# FV1_Touch.net
KiCad netlist of a schematic drawn in EAGLE
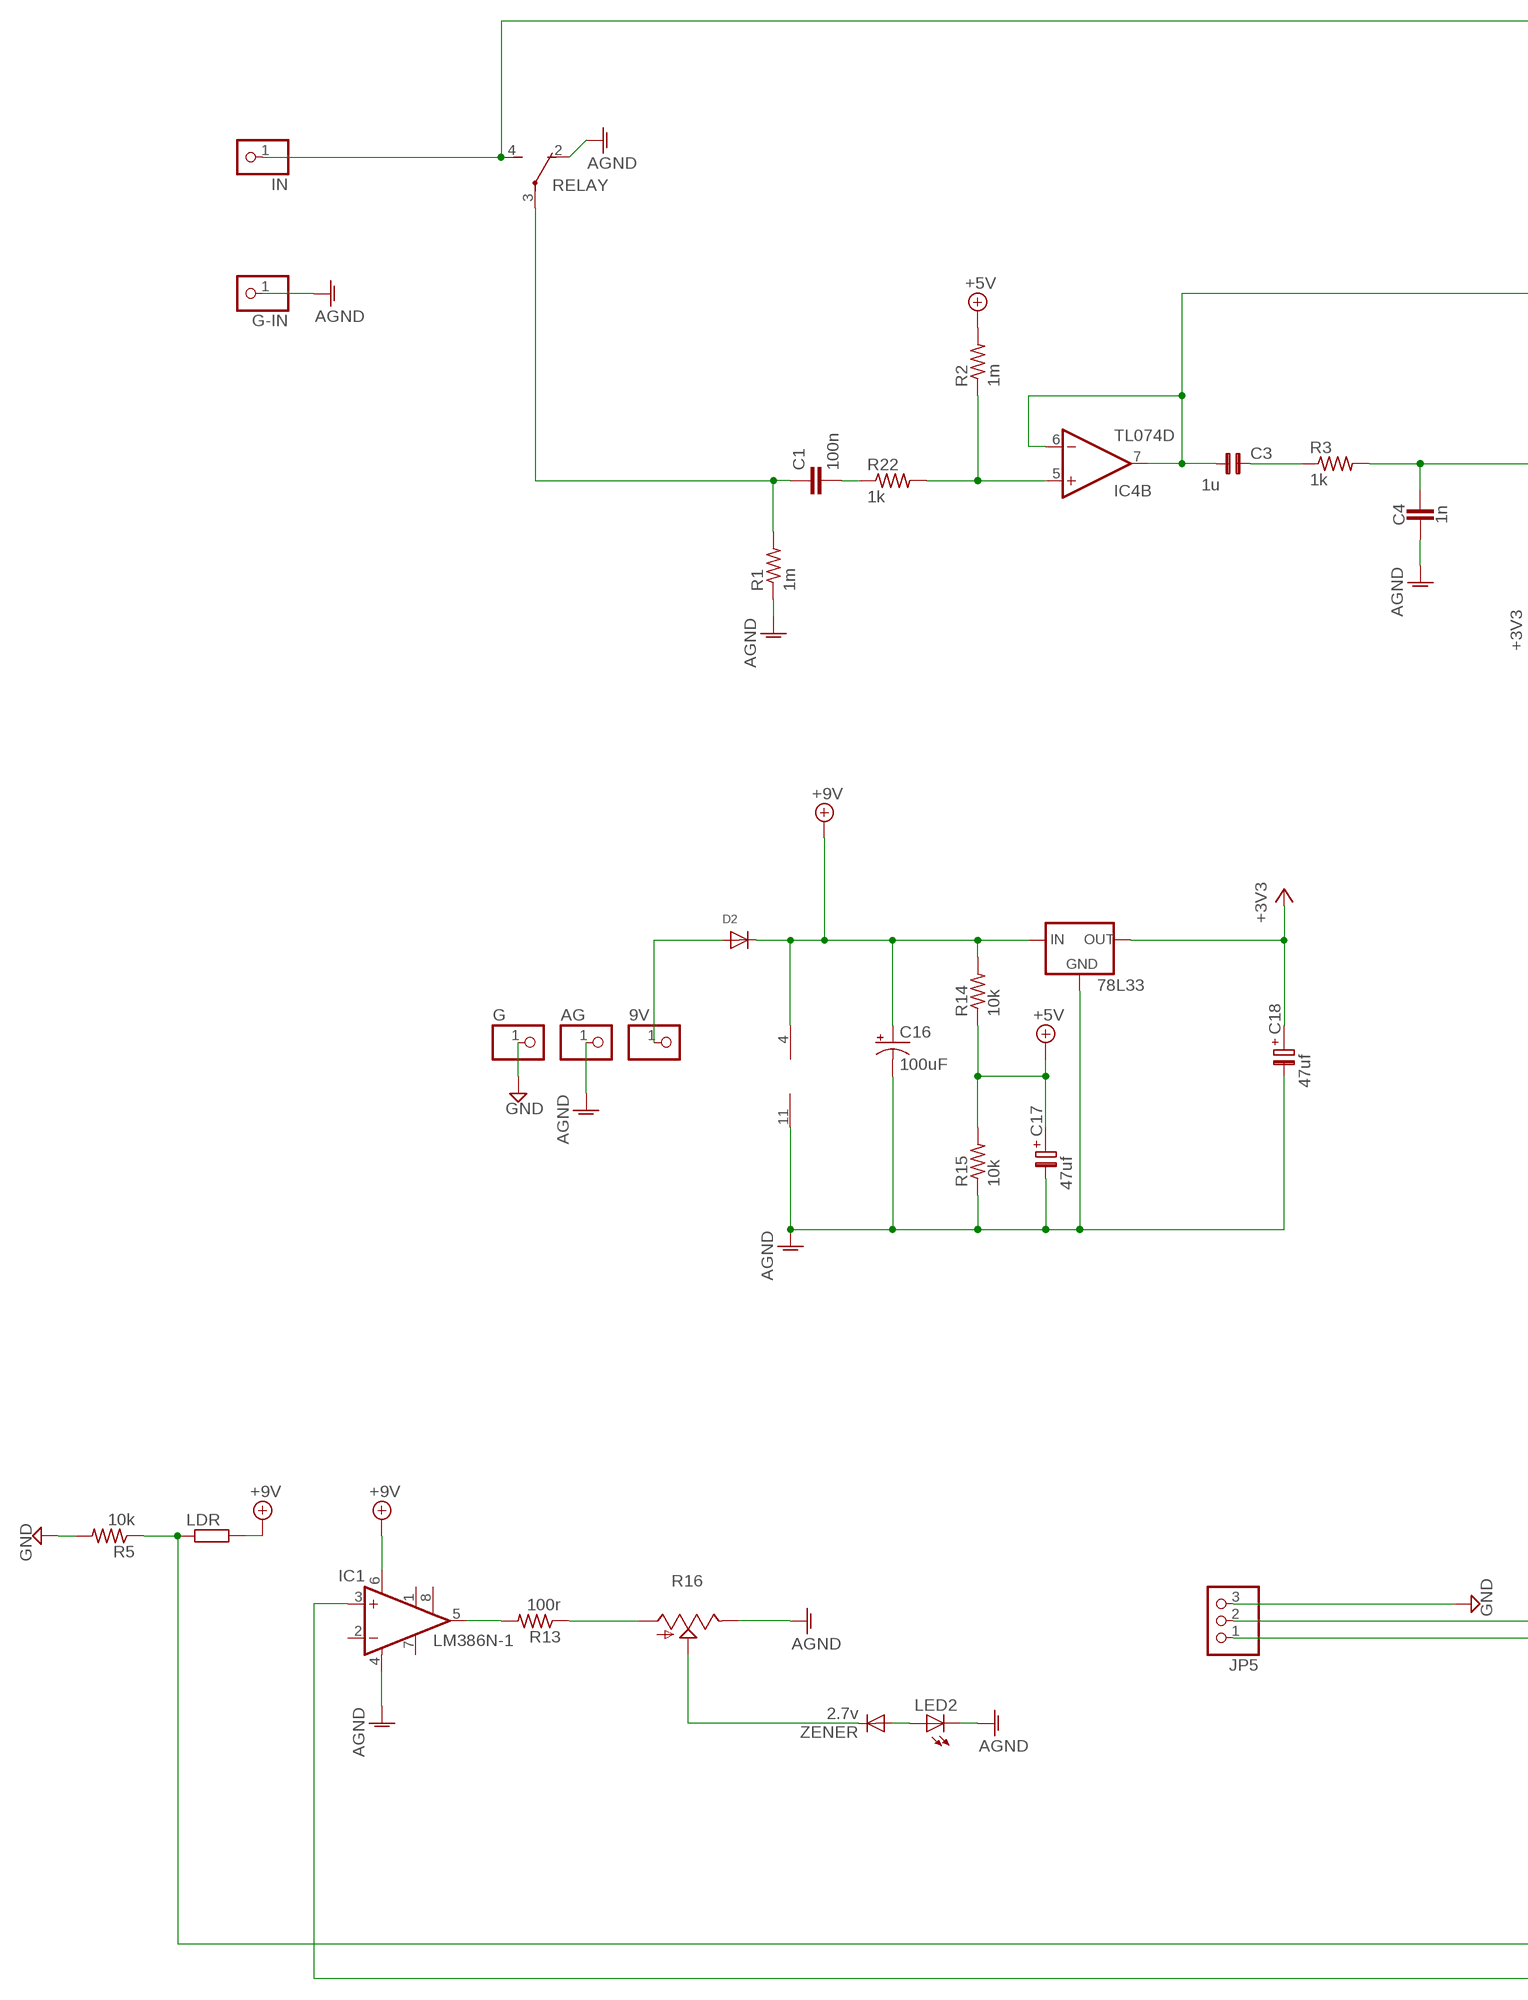
[diagram p0: schematic, sheet 1, part 1 of 2]
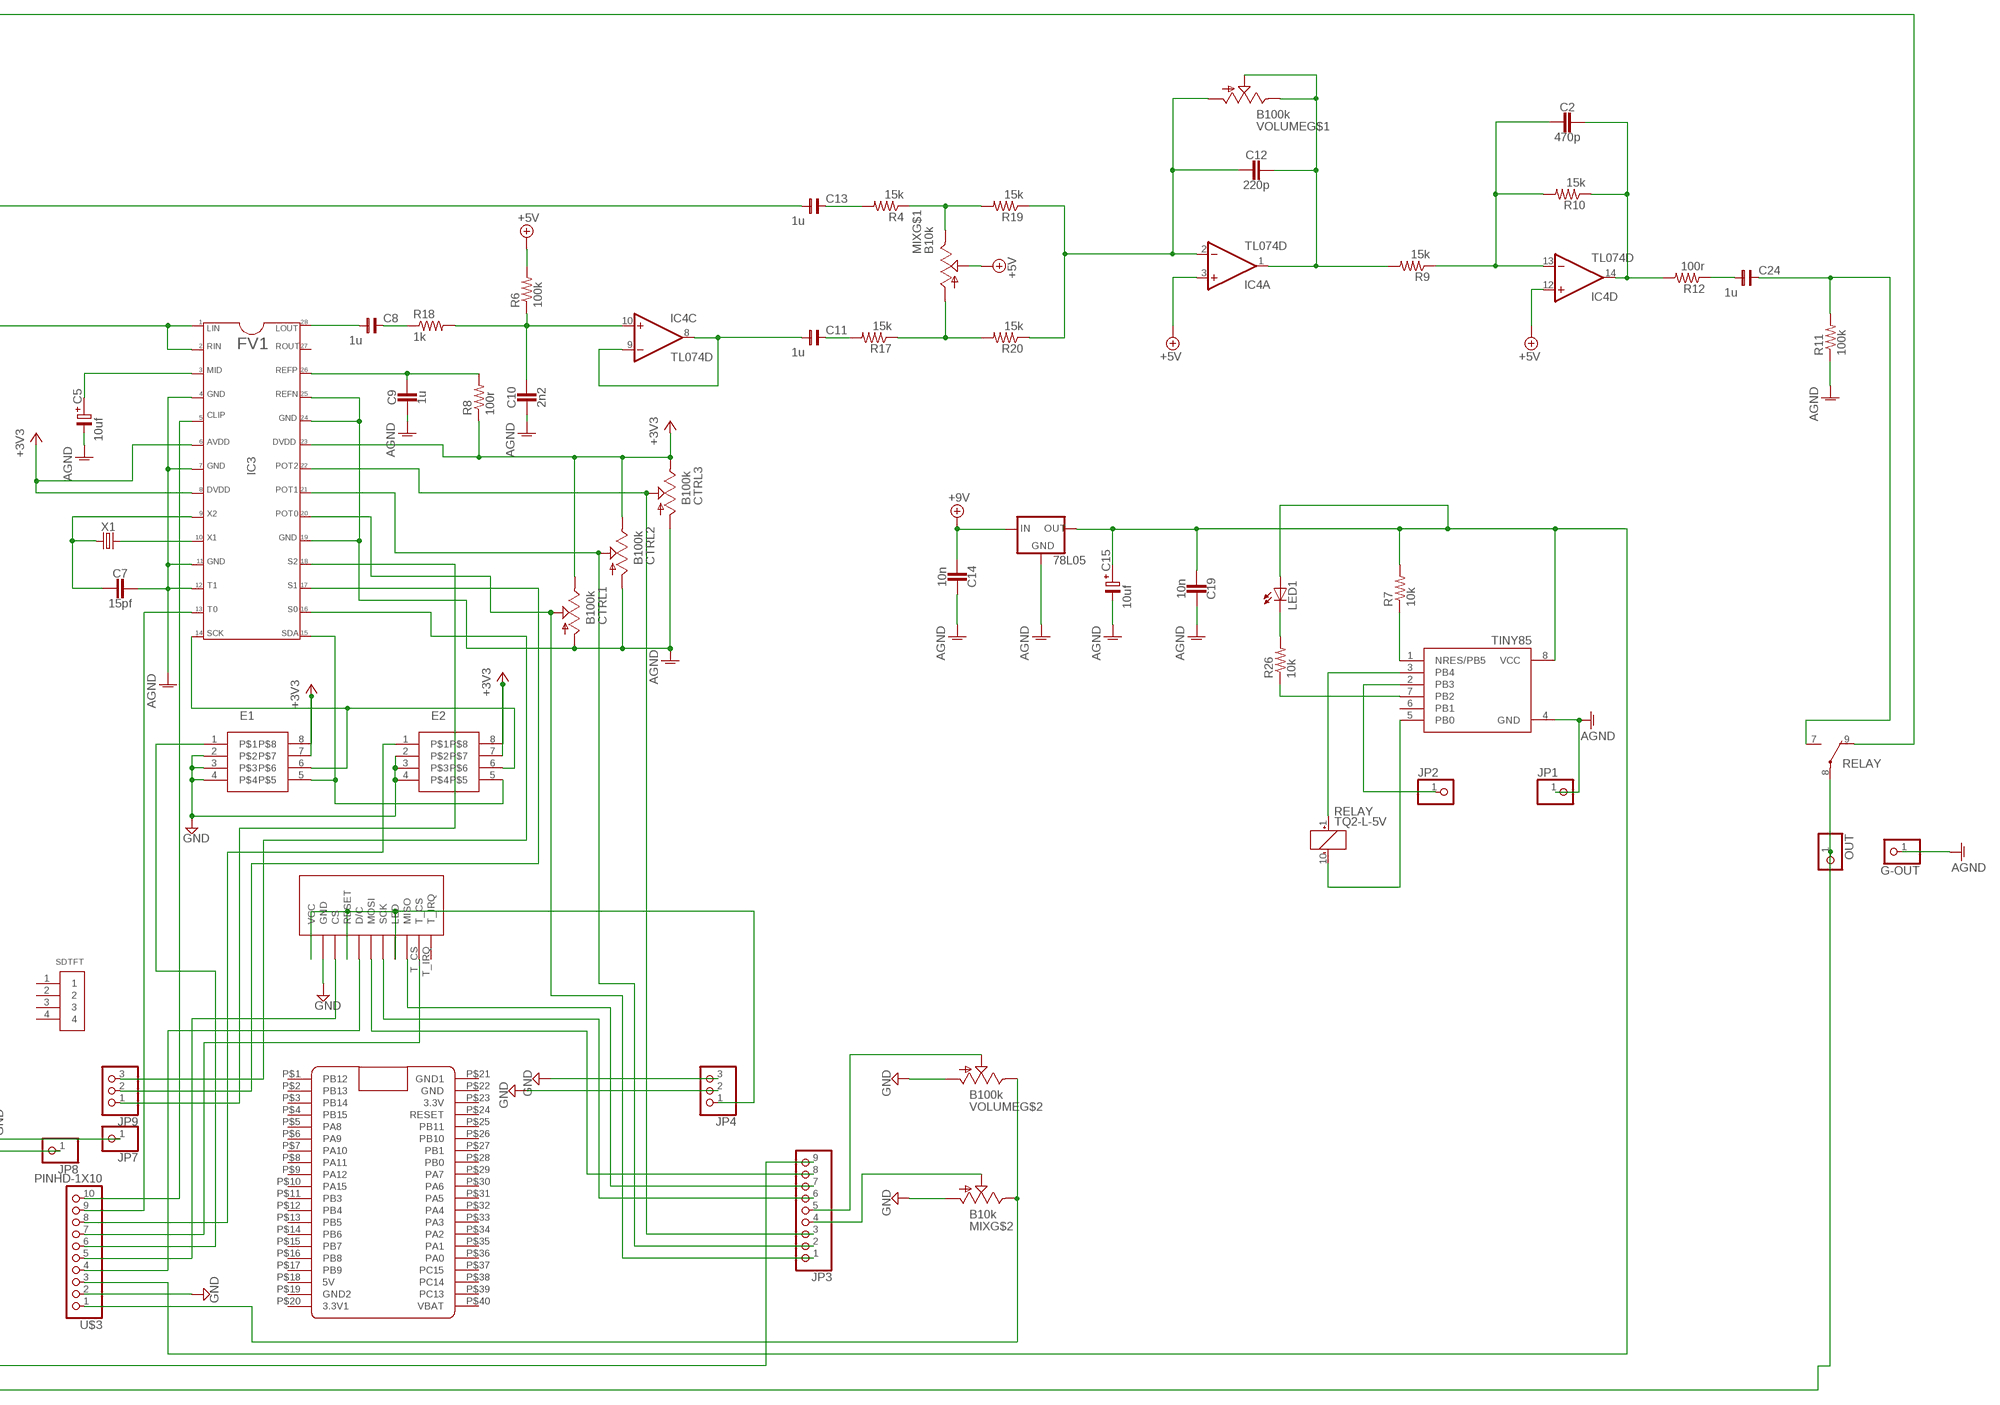
[diagram p1: schematic, sheet 1, part 2 of 2]

(export (version "E")
  (design (tool "Eeschema 10.0.6"))
  (components
    (comp (ref "9V")
      (value "PINHD-1X1")
      (footprint "eagle-import:1X01")
      (libsource (lib "eagle-import") (part "PINHD-1X1"))
    )
    (comp (ref "78L05")
      (value "78LXX-SOT89")
      (footprint "eagle-import:SOT89")
      (libsource (lib "eagle-import") (part "78LXX-SOT89"))
    )
    (comp (ref "78L33")
      (value "78LXX-SOT89")
      (footprint "eagle-import:SOT89")
      (libsource (lib "eagle-import") (part "78LXX-SOT89"))
    )
    (comp (ref "AG")
      (value "PINHD-1X1")
      (footprint "eagle-import:1X01")
      (libsource (lib "eagle-import") (part "PINHD-1X1"))
    )
    (comp (ref "C1")
      (value "100n")
      (footprint "eagle-import:C5B3")
      (libsource (lib "eagle-import") (part "C5/3"))
    )
    (comp (ref "C2")
      (value "470p")
      (footprint "eagle-import:RESISTOR_C1206")
      (libsource (lib "eagle-import") (part "CAP1206"))
    )
    (comp (ref "C3")
      (value "1u")
      (footprint "eagle-import:C5,0-7,5X3,0")
      (libsource (lib "eagle-import") (part "C-NP-5,0-7,5X3,0"))
    )
    (comp (ref "C4")
      (value "1n")
      (footprint "eagle-import:RESISTOR_C1206")
      (libsource (lib "eagle-import") (part "CAP1206"))
    )
    (comp (ref "C5")
      (value "10uf")
      (footprint "eagle-import:SV-C")
      (libsource (lib "eagle-import") (part "C-PR-SMD-SV-C"))
    )
    (comp (ref "C7")
      (value "15pf")
      (footprint "eagle-import:RESISTOR_C1206")
      (libsource (lib "eagle-import") (part "CAP1206"))
    )
    (comp (ref "C8")
      (value "1u")
      (footprint "eagle-import:C5,0-7,5X3,0")
      (libsource (lib "eagle-import") (part "C-NP-5,0-7,5X3,0"))
    )
    (comp (ref "C9")
      (value "1u")
      (footprint "eagle-import:RESISTOR_C1206")
      (libsource (lib "eagle-import") (part "CAP1206"))
    )
    (comp (ref "C10")
      (value "2n2")
      (footprint "eagle-import:RESISTOR_C1206")
      (libsource (lib "eagle-import") (part "CAP1206"))
    )
    (comp (ref "C11")
      (value "1u")
      (footprint "eagle-import:C5,0-7,5X3,0")
      (libsource (lib "eagle-import") (part "C-NP-5,0-7,5X3,0"))
    )
    (comp (ref "C12")
      (value "220p")
      (footprint "eagle-import:RESISTOR_C1206")
      (libsource (lib "eagle-import") (part "CAP1206"))
    )
    (comp (ref "C13")
      (value "1u")
      (footprint "eagle-import:C5,0-7,5X3,0")
      (libsource (lib "eagle-import") (part "C-NP-5,0-7,5X3,0"))
    )
    (comp (ref "C14")
      (value "10n")
      (footprint "eagle-import:RESISTOR_C1206")
      (libsource (lib "eagle-import") (part "CAP1206"))
    )
    (comp (ref "C15")
      (value "10uf")
      (footprint "eagle-import:SV-C")
      (libsource (lib "eagle-import") (part "C-PR-SMD-SV-C"))
    )
    (comp (ref "C16")
      (value "100uF")
      (footprint "eagle-import:PANASONIC_D")
      (libsource (lib "eagle-import") (part "100UF-POLAR-25V-20%(ELEC)"))
    )
    (comp (ref "C17")
      (value "47uf")
      (footprint "eagle-import:SV-C")
      (libsource (lib "eagle-import") (part "C-PR-SMD-SV-C"))
    )
    (comp (ref "C18")
      (value "47uf")
      (footprint "eagle-import:SV-C")
      (libsource (lib "eagle-import") (part "C-PR-SMD-SV-C"))
    )
    (comp (ref "C19")
      (value "10n")
      (footprint "eagle-import:RESISTOR_C1206")
      (libsource (lib "eagle-import") (part "CAP1206"))
    )
    (comp (ref "C24")
      (value "1u")
      (footprint "eagle-import:C5,0-7,5X3,0")
      (libsource (lib "eagle-import") (part "C-NP-5,0-7,5X3,0"))
    )
    (comp (ref "CTRL1")
      (value "B100k")
      (footprint "eagle-import:9MM_SNAP-IN_POT")
      (libsource (lib "eagle-import") (part "9MM_SNAP-IN_POT_"))
    )
    (comp (ref "CTRL2")
      (value "B100k")
      (footprint "eagle-import:9MM_SNAP-IN_POT")
      (libsource (lib "eagle-import") (part "9MM_SNAP-IN_POT_"))
    )
    (comp (ref "CTRL3")
      (value "B100k")
      (footprint "eagle-import:9MM_SNAP-IN_POT")
      (libsource (lib "eagle-import") (part "9MM_SNAP-IN_POT_"))
    )
    (comp (ref "D2")
      (value "DIODESOD-123")
      (footprint "eagle-import:SOD-123")
      (libsource (lib "eagle-import") (part "DIODESOD-123"))
    )
    (comp (ref "E1")
      (value "-EEPROM")
      (footprint "eagle-import:SOCKED-08")
      (libsource (lib "eagle-import") (part "-EEPROM"))
    )
    (comp (ref "E2")
      (value "-EEPROM")
      (footprint "eagle-import:SOCKED-08")
      (libsource (lib "eagle-import") (part "-EEPROM"))
    )
    (comp (ref "G")
      (value "PINHD-1X1")
      (footprint "eagle-import:1X01")
      (libsource (lib "eagle-import") (part "PINHD-1X1"))
    )
    (comp (ref "G-IN")
      (value "PINHD-1X1")
      (footprint "eagle-import:1X01")
      (libsource (lib "eagle-import") (part "PINHD-1X1"))
    )
    (comp (ref "G-OUT")
      (value "PINHD-1X1")
      (footprint "eagle-import:1X01")
      (libsource (lib "eagle-import") (part "PINHD-1X1"))
    )
    (comp (ref "IC1")
      (value "LM386N-1")
      (footprint "eagle-import:DIL08")
      (libsource (lib "eagle-import") (part "LM386?-N1"))
    )
    (comp (ref "IC3")
      (value "FV1")
      (footprint "eagle-import:SO1C28")
      (libsource (lib "eagle-import") (part "FV1"))
    )
    (comp (ref "IC4")
      (value "TL074D")
      (footprint "eagle-import:SO14")
      (libsource (lib "eagle-import") (part "TL074D"))
    )
    (comp (ref "IN")
      (value "PINHD-1X1")
      (footprint "eagle-import:1X01")
      (libsource (lib "eagle-import") (part "PINHD-1X1"))
    )
    (comp (ref "J1")
      (value "SPI_TFT_DISPLAY_TOUCH")
      (footprint "eagle-import:SPI_DISPLAY_TOUCH")
      (libsource (lib "eagle-import") (part "SPI_TFT_DISPLAY_TOUCH"))
    )
    (comp (ref "JP1")
      (value "PINHD-1X1CB")
      (footprint "eagle-import:1X01-CLEANBIG")
      (libsource (lib "eagle-import") (part "PINHD-1X1CB"))
    )
    (comp (ref "JP2")
      (value "PINHD-1X1CB")
      (footprint "eagle-import:1X01-CLEANBIG")
      (libsource (lib "eagle-import") (part "PINHD-1X1CB"))
    )
    (comp (ref "JP3")
      (value "PINHD-1X9")
      (footprint "eagle-import:1X09-BIG")
      (libsource (lib "eagle-import") (part "PINHD-1X9"))
    )
    (comp (ref "JP4")
      (value "PINHD-1X3")
      (footprint "eagle-import:1X03")
      (libsource (lib "eagle-import") (part "PINHD-1X3"))
    )
    (comp (ref "JP5")
      (value "PINHD-1X3")
      (footprint "eagle-import:1X03")
      (libsource (lib "eagle-import") (part "PINHD-1X3"))
    )
    (comp (ref "JP7")
      (value "PINHD-1X1")
      (footprint "eagle-import:1X01")
      (libsource (lib "eagle-import") (part "PINHD-1X1"))
    )
    (comp (ref "JP8")
      (value "PINHD-1X1")
      (footprint "eagle-import:1X01")
      (libsource (lib "eagle-import") (part "PINHD-1X1"))
    )
    (comp (ref "JP9")
      (value "PINHD-1X3")
      (footprint "eagle-import:1X03")
      (libsource (lib "eagle-import") (part "PINHD-1X3"))
    )
    (comp (ref "LDR")
      (value "R-EU_0204/5")
      (footprint "eagle-import:0204_5")
      (libsource (lib "eagle-import") (part "R-EU_0204/5"))
    )
    (comp (ref "LED1")
      (value "LED5MM")
      (footprint "eagle-import:LED5MM")
      (libsource (lib "eagle-import") (part "LED5MM"))
    )
    (comp (ref "LED2")
      (value "LED5MM")
      (footprint "eagle-import:LED5MM")
      (libsource (lib "eagle-import") (part "LED5MM"))
    )
    (comp (ref "MIX")
      (value "B10k")
      (footprint "eagle-import:DUAL_9MM_SNAP-IN_POT")
      (libsource (lib "eagle-import") (part "ALPHA-9MM-DUALPOT"))
    )
    (comp (ref "OUT")
      (value "PINHD-1X1")
      (footprint "eagle-import:1X01")
      (libsource (lib "eagle-import") (part "PINHD-1X1"))
    )
    (comp (ref "R1")
      (value "1m")
      (footprint "eagle-import:R0805")
      (libsource (lib "eagle-import") (part "R-US_R0805"))
    )
    (comp (ref "R2")
      (value "1m")
      (footprint "eagle-import:R0805")
      (libsource (lib "eagle-import") (part "R-US_R0805"))
    )
    (comp (ref "R3")
      (value "1k")
      (footprint "eagle-import:R0805")
      (libsource (lib "eagle-import") (part "R-US_R0805"))
    )
    (comp (ref "R4")
      (value "15k")
      (footprint "eagle-import:R0805")
      (libsource (lib "eagle-import") (part "R-US_R0805"))
    )
    (comp (ref "R5")
      (value "10k")
      (footprint "eagle-import:R0805")
      (libsource (lib "eagle-import") (part "R-US_R0805"))
    )
    (comp (ref "R6")
      (value "100k")
      (footprint "eagle-import:R0805")
      (libsource (lib "eagle-import") (part "R-US_R0805"))
    )
    (comp (ref "R7")
      (value "10k")
      (footprint "eagle-import:R0805")
      (libsource (lib "eagle-import") (part "R-US_R0805"))
    )
    (comp (ref "R8")
      (value "100r")
      (footprint "eagle-import:R0805")
      (libsource (lib "eagle-import") (part "R-US_R0805"))
    )
    (comp (ref "R9")
      (value "15k")
      (footprint "eagle-import:R0805")
      (libsource (lib "eagle-import") (part "R-US_R0805"))
    )
    (comp (ref "R10")
      (value "15k")
      (footprint "eagle-import:R0805")
      (libsource (lib "eagle-import") (part "R-US_R0805"))
    )
    (comp (ref "R11")
      (value "100k")
      (footprint "eagle-import:R0805")
      (libsource (lib "eagle-import") (part "R-US_R0805"))
    )
    (comp (ref "R12")
      (value "100r")
      (footprint "eagle-import:R0805")
      (libsource (lib "eagle-import") (part "R-US_R0805"))
    )
    (comp (ref "R13")
      (value "100r")
      (footprint "eagle-import:R0805")
      (libsource (lib "eagle-import") (part "R-US_R0805"))
    )
    (comp (ref "R14")
      (value "10k")
      (footprint "eagle-import:R0805")
      (libsource (lib "eagle-import") (part "R-US_R0805"))
    )
    (comp (ref "R15")
      (value "10k")
      (footprint "eagle-import:R0805")
      (libsource (lib "eagle-import") (part "R-US_R0805"))
    )
    (comp (ref "R16")
      (value "TRIM_US-B25P")
      (footprint "eagle-import:B25P")
      (libsource (lib "eagle-import") (part "TRIM_US-B25P"))
    )
    (comp (ref "R17")
      (value "15k")
      (footprint "eagle-import:R0805")
      (libsource (lib "eagle-import") (part "R-US_R0805"))
    )
    (comp (ref "R18")
      (value "1k")
      (footprint "eagle-import:R0805")
      (libsource (lib "eagle-import") (part "R-US_R0805"))
    )
    (comp (ref "R19")
      (value "15k")
      (footprint "eagle-import:R0805")
      (libsource (lib "eagle-import") (part "R-US_R0805"))
    )
    (comp (ref "R20")
      (value "15k")
      (footprint "eagle-import:R0805")
      (libsource (lib "eagle-import") (part "R-US_R0805"))
    )
    (comp (ref "R22")
      (value "1k")
      (footprint "eagle-import:R0805")
      (libsource (lib "eagle-import") (part "R-US_R0805"))
    )
    (comp (ref "R26")
      (value "10k")
      (footprint "eagle-import:R0805")
      (libsource (lib "eagle-import") (part "R-US_R0805"))
    )
    (comp (ref "RELAY")
      (value "TQ2-L-5V")
      (footprint "eagle-import:TQ2")
      (libsource (lib "eagle-import") (part "TQ2?-5V"))
    )
    (comp (ref "SDTFT")
      (value "1X4-BIG")
      (footprint "eagle-import:1X04-BIG")
      (libsource (lib "eagle-import") (part "1X4-BIG"))
    )
    (comp (ref "TINY85")
      (value "ATTINY85-20P")
      (footprint "eagle-import:PDIP08_300MIL")
      (libsource (lib "eagle-import") (part "ATTINY85P-20"))
    )
    (comp (ref "U$1")
      (value "BLUE_PILL")
      (footprint "eagle-import:BLUE_PILL")
      (libsource (lib "eagle-import") (part "BLUE_PILL"))
    )
    (comp (ref "U$3")
      (value "PINHD-1X10")
      (footprint "eagle-import:1X10-BIG")
      (libsource (lib "eagle-import") (part "PINHD-1X10"))
    )
    (comp (ref "VOLUME")
      (value "B100k")
      (footprint "eagle-import:DUAL_9MM_SNAP-IN_POT")
      (libsource (lib "eagle-import") (part "ALPHA-9MM-DUALPOT"))
    )
    (comp (ref "X1")
      (value "CRYSTALPTH-2X6-KIT")
      (footprint "eagle-import:CRYSTAL-PTH-2X6-CYL-KIT")
      (libsource (lib "eagle-import") (part "CRYSTALPTH-2X6-KIT"))
    )
    (comp (ref "ZENER")
      (value "2.7v")
      (footprint "eagle-import:DO35-7")
      (libsource (lib "eagle-import") (part "SMALL_DIODEDO35-7"))
    )
  )
  (nets
    (net (code "1") (name "+3V3") (class "Default")
      (node (ref "78L33") (pin "1") (pinfunction "OUT_1") (pintype "passive"))
      (node (ref "C18") (pin "+") (pinfunction "+_+") (pintype "passive"))
      (node (ref "CTRL1") (pin "3") (pinfunction "E_3") (pintype "passive"))
      (node (ref "CTRL2") (pin "3") (pinfunction "E_3") (pintype "passive"))
      (node (ref "CTRL3") (pin "3") (pinfunction "E_3") (pintype "passive"))
      (node (ref "E1") (pin "7") (pinfunction "P$7_7") (pintype "bidirectional"))
      (node (ref "E1") (pin "8") (pinfunction "P$8_8") (pintype "bidirectional"))
      (node (ref "E2") (pin "7") (pinfunction "P$7_7") (pintype "bidirectional"))
      (node (ref "E2") (pin "8") (pinfunction "P$8_8") (pintype "bidirectional"))
      (node (ref "IC3") (pin "23") (pinfunction "P$23_23") (pintype "bidirectional"))
      (node (ref "IC3") (pin "6") (pinfunction "P$6_6") (pintype "bidirectional"))
      (node (ref "IC3") (pin "8") (pinfunction "P$8_8") (pintype "bidirectional"))
      (node (ref "R8") (pin "1") (pinfunction "1_1") (pintype "passive"))
    )
    (net (code "2") (name "+5V") (class "Default")
      (node (ref "C17") (pin "+") (pinfunction "+_+") (pintype "passive"))
      (node (ref "IC4") (pin "12") (pinfunction "+IN_12") (pintype "input"))
      (node (ref "IC4") (pin "3") (pinfunction "+IN_3") (pintype "input"))
      (node (ref "MIX") (pin "2") (pinfunction "S_2") (pintype "passive"))
      (node (ref "R14") (pin "1") (pinfunction "1_1") (pintype "passive"))
      (node (ref "R15") (pin "2") (pinfunction "2_2") (pintype "passive"))
      (node (ref "R2") (pin "2") (pinfunction "2_2") (pintype "passive"))
      (node (ref "R6") (pin "2") (pinfunction "2_2") (pintype "passive"))
    )
    (net (code "3") (name "+9V") (class "Default")
      (node (ref "78L05") (pin "3") (pinfunction "IN_3") (pintype "input"))
      (node (ref "78L33") (pin "3") (pinfunction "IN_3") (pintype "input"))
      (node (ref "C14") (pin "2") (pinfunction "2_2") (pintype "passive"))
      (node (ref "C16") (pin "+") (pinfunction "+_+") (pintype "passive"))
      (node (ref "D2") (pin "C") (pinfunction "C_C") (pintype "passive"))
      (node (ref "IC1") (pin "6") (pinfunction "VS_6") (pintype "power_in"))
      (node (ref "IC4") (pin "4") (pinfunction "V+_4") (pintype "power_in"))
      (node (ref "LDR") (pin "2") (pinfunction "2_2") (pintype "passive"))
      (node (ref "R14") (pin "2") (pinfunction "2_2") (pintype "passive"))
    )
    (net (code "4") (name "/GND1") (class "Default")
      (node (ref "U$1") (pin "P$21") (pinfunction "GND1_P$21") (pintype "power_in"))
    )
    (net (code "5") (name "AGND") (class "Default")
      (node (ref "78L05") (pin "2") (pinfunction "GND_2") (pintype "input"))
      (node (ref "78L33") (pin "2") (pinfunction "GND_2") (pintype "input"))
      (node (ref "AG") (pin "1") (pinfunction "1_1") (pintype "passive"))
      (node (ref "C10") (pin "2") (pinfunction "2_2") (pintype "passive"))
      (node (ref "C14") (pin "1") (pinfunction "1_1") (pintype "passive"))
      (node (ref "C15") (pin "-") (pinfunction "-_-") (pintype "passive"))
      (node (ref "C16") (pin "-") (pinfunction "-_-") (pintype "passive"))
      (node (ref "C17") (pin "-") (pinfunction "-_-") (pintype "passive"))
      (node (ref "C18") (pin "-") (pinfunction "-_-") (pintype "passive"))
      (node (ref "C19") (pin "1") (pinfunction "1_1") (pintype "passive"))
      (node (ref "C4") (pin "2") (pinfunction "2_2") (pintype "passive"))
      (node (ref "C5") (pin "-") (pinfunction "-_-") (pintype "passive"))
      (node (ref "C7") (pin "1") (pinfunction "1_1") (pintype "passive"))
      (node (ref "C9") (pin "2") (pinfunction "2_2") (pintype "passive"))
      (node (ref "CTRL1") (pin "1") (pinfunction "A_1") (pintype "passive"))
      (node (ref "CTRL2") (pin "1") (pinfunction "A_1") (pintype "passive"))
      (node (ref "CTRL3") (pin "1") (pinfunction "A_1") (pintype "passive"))
      (node (ref "G-IN") (pin "1") (pinfunction "1_1") (pintype "passive"))
      (node (ref "G-OUT") (pin "1") (pinfunction "1_1") (pintype "passive"))
      (node (ref "IC1") (pin "4") (pinfunction "GND_4") (pintype "power_in"))
      (node (ref "IC3") (pin "11") (pinfunction "P$11_11") (pintype "bidirectional"))
      (node (ref "IC3") (pin "12") (pinfunction "P$12_12") (pintype "bidirectional"))
      (node (ref "IC3") (pin "19") (pinfunction "P$19_19") (pintype "bidirectional"))
      (node (ref "IC3") (pin "24") (pinfunction "P$24_24") (pintype "bidirectional"))
      (node (ref "IC3") (pin "25") (pinfunction "P$25_25") (pintype "bidirectional"))
      (node (ref "IC3") (pin "4") (pinfunction "P$4_4") (pintype "bidirectional"))
      (node (ref "IC3") (pin "7") (pinfunction "P$7_7") (pintype "bidirectional"))
      (node (ref "IC4") (pin "11") (pinfunction "V-_11") (pintype "power_in"))
      (node (ref "JP1") (pin "1") (pinfunction "1_1") (pintype "passive"))
      (node (ref "LED2") (pin "K") (pinfunction "C_K") (pintype "passive"))
      (node (ref "R1") (pin "1") (pinfunction "1_1") (pintype "passive"))
      (node (ref "R11") (pin "1") (pinfunction "1_1") (pintype "passive"))
      (node (ref "R15") (pin "1") (pinfunction "1_1") (pintype "passive"))
      (node (ref "R16") (pin "E") (pinfunction "E_E") (pintype "passive"))
      (node (ref "RELAY") (pin "2") (pinfunction "O_2") (pintype "passive"))
      (node (ref "TINY85") (pin "4") (pinfunction "GND_4") (pintype "power_in"))
    )
    (net (code "6") (name "GND") (class "Default")
      (node (ref "E1") (pin "2") (pinfunction "P$2_2") (pintype "bidirectional"))
      (node (ref "E1") (pin "3") (pinfunction "P$3_3") (pintype "bidirectional"))
      (node (ref "E1") (pin "4") (pinfunction "P$4_4") (pintype "bidirectional"))
      (node (ref "E2") (pin "2") (pinfunction "P$2_2") (pintype "bidirectional"))
      (node (ref "E2") (pin "3") (pinfunction "P$3_3") (pintype "bidirectional"))
      (node (ref "E2") (pin "4") (pinfunction "P$4_4") (pintype "bidirectional"))
      (node (ref "G") (pin "1") (pinfunction "1_1") (pintype "passive"))
      (node (ref "J1") (pin "GND") (pinfunction "GND_GND") (pintype "power_in"))
      (node (ref "JP4") (pin "2") (pinfunction "2_2") (pintype "passive"))
      (node (ref "JP4") (pin "3") (pinfunction "3_3") (pintype "passive"))
      (node (ref "JP5") (pin "3") (pinfunction "3_3") (pintype "passive"))
      (node (ref "MIX") (pin "1B") (pinfunction "A_1B") (pintype "passive"))
      (node (ref "R5") (pin "2") (pinfunction "2_2") (pintype "passive"))
      (node (ref "U$3") (pin "2") (pinfunction "2_2") (pintype "passive"))
      (node (ref "VOLUME") (pin "1B") (pinfunction "A_1B") (pintype "passive"))
    )
    (net (code "7") (name "Net-(9V-Pad1)") (class "Default")
      (node (ref "9V") (pin "1") (pinfunction "1_1") (pintype "passive"))
      (node (ref "D2") (pin "A") (pinfunction "A_A") (pintype "passive"))
    )
    (net (code "8") (name "Net-(78L05-OUT)") (class "Default")
      (node (ref "78L05") (pin "1") (pinfunction "OUT_1") (pintype "passive"))
      (node (ref "C15") (pin "+") (pinfunction "+_+") (pintype "passive"))
      (node (ref "C19") (pin "2") (pinfunction "2_2") (pintype "passive"))
      (node (ref "LED1") (pin "A") (pinfunction "A_A") (pintype "passive"))
      (node (ref "R7") (pin "2") (pinfunction "2_2") (pintype "passive"))
      (node (ref "TINY85") (pin "8") (pinfunction "VCC_8") (pintype "power_in"))
      (node (ref "U$3") (pin "3") (pinfunction "3_3") (pintype "passive"))
    )
    (net (code "9") (name "Net-(C1-Pad2)") (class "Default")
      (node (ref "C1") (pin "2") (pinfunction "2_2") (pintype "passive"))
      (node (ref "R22") (pin "1") (pinfunction "1_1") (pintype "passive"))
    )
    (net (code "10") (name "Net-(C3-Pad2)") (class "Default")
      (node (ref "C3") (pin "2") (pinfunction "2_2") (pintype "passive"))
      (node (ref "R3") (pin "1") (pinfunction "1_1") (pintype "passive"))
    )
    (net (code "11") (name "Net-(C8-Pad2)") (class "Default")
      (node (ref "C8") (pin "2") (pinfunction "2_2") (pintype "passive"))
      (node (ref "R18") (pin "1") (pinfunction "1_1") (pintype "passive"))
    )
    (net (code "12") (name "Net-(C11-Pad2)") (class "Default")
      (node (ref "C11") (pin "2") (pinfunction "2_2") (pintype "passive"))
      (node (ref "R17") (pin "2") (pinfunction "2_2") (pintype "passive"))
    )
    (net (code "13") (name "Net-(C13-Pad2)") (class "Default")
      (node (ref "C13") (pin "2") (pinfunction "2_2") (pintype "passive"))
      (node (ref "R4") (pin "2") (pinfunction "2_2") (pintype "passive"))
    )
    (net (code "14") (name "Net-(C24-Pad1)") (class "Default")
      (node (ref "C24") (pin "1") (pinfunction "1_1") (pintype "passive"))
      (node (ref "R12") (pin "1") (pinfunction "1_1") (pintype "passive"))
    )
    (net (code "15") (name "Net-(CTRL1-S)") (class "Default")
      (node (ref "CTRL1") (pin "2") (pinfunction "S_2") (pintype "passive"))
      (node (ref "IC3") (pin "20") (pinfunction "P$20_20") (pintype "bidirectional"))
      (node (ref "JP3") (pin "1") (pinfunction "1_1") (pintype "passive"))
    )
    (net (code "16") (name "Net-(CTRL2-S)") (class "Default")
      (node (ref "CTRL2") (pin "2") (pinfunction "S_2") (pintype "passive"))
      (node (ref "IC3") (pin "21") (pinfunction "P$21_21") (pintype "bidirectional"))
      (node (ref "JP3") (pin "2") (pinfunction "2_2") (pintype "passive"))
    )
    (net (code "17") (name "Net-(CTRL3-S)") (class "Default")
      (node (ref "CTRL3") (pin "2") (pinfunction "S_2") (pintype "passive"))
      (node (ref "IC3") (pin "22") (pinfunction "P$22_22") (pintype "bidirectional"))
      (node (ref "JP3") (pin "3") (pinfunction "3_3") (pintype "passive"))
    )
    (net (code "18") (name "Net-(E1-P$1)") (class "Default")
      (node (ref "E1") (pin "1") (pinfunction "P$1_1") (pintype "bidirectional"))
      (node (ref "U$3") (pin "6") (pinfunction "6_6") (pintype "passive"))
    )
    (net (code "19") (name "Net-(E1-P$5)") (class "Default")
      (node (ref "E1") (pin "5") (pinfunction "P$5_5") (pintype "bidirectional"))
      (node (ref "E2") (pin "5") (pinfunction "P$5_5") (pintype "bidirectional"))
      (node (ref "IC3") (pin "15") (pinfunction "P$15_15") (pintype "bidirectional"))
    )
    (net (code "20") (name "Net-(E1-P$6)") (class "Default")
      (node (ref "E1") (pin "6") (pinfunction "P$6_6") (pintype "bidirectional"))
      (node (ref "E2") (pin "6") (pinfunction "P$6_6") (pintype "bidirectional"))
      (node (ref "IC3") (pin "14") (pinfunction "P$14_14") (pintype "bidirectional"))
    )
    (net (code "21") (name "Net-(E2-P$1)") (class "Default")
      (node (ref "E2") (pin "1") (pinfunction "P$1_1") (pintype "bidirectional"))
      (node (ref "U$3") (pin "8") (pinfunction "8_8") (pintype "passive"))
    )
    (net (code "22") (name "Net-(IC1-+IN)") (class "Default")
      (node (ref "IC1") (pin "3") (pinfunction "+IN_3") (pintype "input"))
      (node (ref "OUT") (pin "1") (pinfunction "1_1") (pintype "passive"))
      (node (ref "RELAY") (pin "8") (pinfunction "P_8") (pintype "passive"))
    )
    (net (code "23") (name "Net-(IC1-OUT)") (class "Default")
      (node (ref "IC1") (pin "5") (pinfunction "OUT_5") (pintype "output"))
      (node (ref "R13") (pin "2") (pinfunction "2_2") (pintype "passive"))
    )
    (net (code "24") (name "Net-(IC3-P$1)") (class "Default")
      (node (ref "C4") (pin "1") (pinfunction "1_1") (pintype "passive"))
      (node (ref "IC3") (pin "1") (pinfunction "P$1_1") (pintype "bidirectional"))
      (node (ref "IC3") (pin "2") (pinfunction "P$2_2") (pintype "bidirectional"))
      (node (ref "R3") (pin "2") (pinfunction "2_2") (pintype "passive"))
    )
    (net (code "25") (name "Net-(IC3-P$3)") (class "Default")
      (node (ref "C5") (pin "+") (pinfunction "+_+") (pintype "passive"))
      (node (ref "IC3") (pin "3") (pinfunction "P$3_3") (pintype "bidirectional"))
    )
    (net (code "26") (name "Net-(IC3-P$5)") (class "Default")
      (node (ref "IC3") (pin "5") (pinfunction "P$5_5") (pintype "bidirectional"))
      (node (ref "U$3") (pin "10") (pinfunction "10_10") (pintype "passive"))
    )
    (net (code "27") (name "Net-(IC3-P$9)") (class "Default")
      (node (ref "C7") (pin "2") (pinfunction "2_2") (pintype "passive"))
      (node (ref "IC3") (pin "9") (pinfunction "P$9_9") (pintype "bidirectional"))
      (node (ref "X1") (pin "1") (pinfunction "1_1") (pintype "passive"))
    )
    (net (code "28") (name "Net-(IC3-P$10)") (class "Default")
      (node (ref "IC3") (pin "10") (pinfunction "P$10_10") (pintype "bidirectional"))
      (node (ref "X1") (pin "2") (pinfunction "2_2") (pintype "passive"))
    )
    (net (code "29") (name "Net-(IC3-P$13)") (class "Default")
      (node (ref "IC3") (pin "13") (pinfunction "P$13_13") (pintype "bidirectional"))
      (node (ref "U$3") (pin "9") (pinfunction "9_9") (pintype "passive"))
    )
    (net (code "30") (name "Net-(IC3-P$16)") (class "Default")
      (node (ref "IC3") (pin "16") (pinfunction "P$16_16") (pintype "bidirectional"))
      (node (ref "JP9") (pin "3") (pinfunction "3_3") (pintype "passive"))
    )
    (net (code "31") (name "Net-(IC3-P$17)") (class "Default")
      (node (ref "IC3") (pin "17") (pinfunction "P$17_17") (pintype "bidirectional"))
      (node (ref "JP9") (pin "2") (pinfunction "2_2") (pintype "passive"))
    )
    (net (code "32") (name "Net-(IC3-P$18)") (class "Default")
      (node (ref "IC3") (pin "18") (pinfunction "P$18_18") (pintype "bidirectional"))
      (node (ref "JP9") (pin "1") (pinfunction "1_1") (pintype "passive"))
    )
    (net (code "33") (name "Net-(IC3-P$26)") (class "Default")
      (node (ref "C9") (pin "1") (pinfunction "1_1") (pintype "passive"))
      (node (ref "IC3") (pin "26") (pinfunction "P$26_26") (pintype "bidirectional"))
      (node (ref "R8") (pin "2") (pinfunction "2_2") (pintype "passive"))
    )
    (net (code "34") (name "Net-(IC3-P$28)") (class "Default")
      (node (ref "C8") (pin "1") (pinfunction "1_1") (pintype "passive"))
      (node (ref "IC3") (pin "28") (pinfunction "P$28_28") (pintype "bidirectional"))
    )
    (net (code "35") (name "Net-(IC4A--IN)") (class "Default")
      (node (ref "C12") (pin "2") (pinfunction "2_2") (pintype "passive"))
      (node (ref "IC4") (pin "2") (pinfunction "-IN_2") (pintype "input"))
      (node (ref "R19") (pin "1") (pinfunction "1_1") (pintype "passive"))
      (node (ref "R20") (pin "1") (pinfunction "1_1") (pintype "passive"))
      (node (ref "VOLUME") (pin "1") (pinfunction "A_1") (pintype "passive"))
    )
    (net (code "36") (name "Net-(IC4A-OUT)") (class "Default")
      (node (ref "C12") (pin "1") (pinfunction "1_1") (pintype "passive"))
      (node (ref "IC4") (pin "1") (pinfunction "OUT_1") (pintype "output"))
      (node (ref "R9") (pin "2") (pinfunction "2_2") (pintype "passive"))
      (node (ref "VOLUME") (pin "2") (pinfunction "S_2") (pintype "passive"))
      (node (ref "VOLUME") (pin "3") (pinfunction "E_3") (pintype "passive"))
    )
    (net (code "37") (name "Net-(IC4B-+IN)") (class "Default")
      (node (ref "IC4") (pin "5") (pinfunction "+IN_5") (pintype "input"))
      (node (ref "R2") (pin "1") (pinfunction "1_1") (pintype "passive"))
      (node (ref "R22") (pin "2") (pinfunction "2_2") (pintype "passive"))
    )
    (net (code "38") (name "Net-(IC4B--IN)") (class "Default")
      (node (ref "C13") (pin "1") (pinfunction "1_1") (pintype "passive"))
      (node (ref "C3") (pin "1") (pinfunction "1_1") (pintype "passive"))
      (node (ref "IC4") (pin "6") (pinfunction "-IN_6") (pintype "input"))
      (node (ref "IC4") (pin "7") (pinfunction "OUT_7") (pintype "output"))
    )
    (net (code "39") (name "Net-(IC4C-+IN)") (class "Default")
      (node (ref "C10") (pin "1") (pinfunction "1_1") (pintype "passive"))
      (node (ref "IC4") (pin "10") (pinfunction "+IN_10") (pintype "input"))
      (node (ref "R18") (pin "2") (pinfunction "2_2") (pintype "passive"))
      (node (ref "R6") (pin "1") (pinfunction "1_1") (pintype "passive"))
    )
    (net (code "40") (name "Net-(IC4C--IN)") (class "Default")
      (node (ref "C11") (pin "1") (pinfunction "1_1") (pintype "passive"))
      (node (ref "IC4") (pin "8") (pinfunction "OUT_8") (pintype "output"))
      (node (ref "IC4") (pin "9") (pinfunction "-IN_9") (pintype "input"))
    )
    (net (code "41") (name "Net-(IC4D--IN)") (class "Default")
      (node (ref "C2") (pin "2") (pinfunction "2_2") (pintype "passive"))
      (node (ref "IC4") (pin "13") (pinfunction "-IN_13") (pintype "input"))
      (node (ref "R10") (pin "2") (pinfunction "2_2") (pintype "passive"))
      (node (ref "R9") (pin "1") (pinfunction "1_1") (pintype "passive"))
    )
    (net (code "42") (name "Net-(IC4D-OUT)") (class "Default")
      (node (ref "C2") (pin "1") (pinfunction "1_1") (pintype "passive"))
      (node (ref "IC4") (pin "14") (pinfunction "OUT_14") (pintype "output"))
      (node (ref "R10") (pin "1") (pinfunction "1_1") (pintype "passive"))
      (node (ref "R12") (pin "2") (pinfunction "2_2") (pintype "passive"))
    )
    (net (code "43") (name "Net-(J1-MISO-PadT_MISO)") (class "Default")
      (node (ref "J1") (pin "MISO") (pinfunction "MISO_MISO") (pintype "bidirectional"))
      (node (ref "J1") (pin "T_MISO") (pinfunction "MISO_T_MISO") (pintype "bidirectional"))
      (node (ref "JP3") (pin "7") (pinfunction "7_7") (pintype "passive"))
    )
    (net (code "44") (name "Net-(J1-MOSI-PadT_MOSI)") (class "Default")
      (node (ref "J1") (pin "MOSI") (pinfunction "MOSI_MOSI") (pintype "bidirectional"))
      (node (ref "J1") (pin "T_MOSI") (pinfunction "MOSI_T_MOSI") (pintype "bidirectional"))
      (node (ref "JP3") (pin "8") (pinfunction "8_8") (pintype "passive"))
    )
    (net (code "45") (name "Net-(J1-PadCS)") (class "Default")
      (node (ref "J1") (pin "CS") (pinfunction "CS_CS") (pintype "bidirectional"))
      (node (ref "U$3") (pin "5") (pinfunction "5_5") (pintype "passive"))
    )
    (net (code "46") (name "Net-(J1-PadD{slash}C)") (class "Default")
      (node (ref "J1") (pin "D/C") (pinfunction "D/C_D/C") (pintype "bidirectional"))
      (node (ref "U$3") (pin "4") (pinfunction "4_4") (pintype "passive"))
    )
    (net (code "47") (name "Net-(J1-PadLED)") (class "Default")
      (node (ref "J1") (pin "LED") (pinfunction "LED_LED") (pintype "bidirectional"))
      (node (ref "J1") (pin "RESET") (pinfunction "RESET_RESET") (pintype "bidirectional"))
      (node (ref "J1") (pin "VCC") (pinfunction "VCC_VCC") (pintype "power_in"))
      (node (ref "JP4") (pin "1") (pinfunction "1_1") (pintype "passive"))
    )
    (net (code "48") (name "Net-(J1-PadSCK)") (class "Default")
      (node (ref "J1") (pin "SCK") (pinfunction "SCK_SCK") (pintype "bidirectional"))
      (node (ref "J1") (pin "T_SCK") (pinfunction "SCK_T_SCK") (pintype "bidirectional"))
      (node (ref "JP3") (pin "6") (pinfunction "6_6") (pintype "passive"))
    )
    (net (code "49") (name "Net-(J1-PadT_CS)") (class "Default")
      (node (ref "J1") (pin "T_CS") (pinfunction "T_CS_T_CS") (pintype "bidirectional"))
      (node (ref "U$3") (pin "7") (pinfunction "7_7") (pintype "passive"))
    )
    (net (code "50") (name "Net-(JP3-Pad9)") (class "Default")
      (node (ref "JP3") (pin "9") (pinfunction "9_9") (pintype "passive"))
      (node (ref "LDR") (pin "1") (pinfunction "1_1") (pintype "passive"))
      (node (ref "R5") (pin "1") (pinfunction "1_1") (pintype "passive"))
    )
    (net (code "51") (name "Net-(JP5-Pad1)") (class "Default")
      (node (ref "JP5") (pin "1") (pinfunction "1_1") (pintype "passive"))
      (node (ref "JP8") (pin "1") (pinfunction "1_1") (pintype "passive"))
    )
    (net (code "52") (name "Net-(JP5-Pad2)") (class "Default")
      (node (ref "JP5") (pin "2") (pinfunction "2_2") (pintype "passive"))
      (node (ref "JP7") (pin "1") (pinfunction "1_1") (pintype "passive"))
    )
    (net (code "53") (name "Net-(LED1-C)") (class "Default")
      (node (ref "LED1") (pin "K") (pinfunction "C_K") (pintype "passive"))
      (node (ref "R26") (pin "2") (pinfunction "2_2") (pintype "passive"))
    )
    (net (code "54") (name "Net-(LED2-PadA)") (class "Default")
      (node (ref "LED2") (pin "A") (pinfunction "A_A") (pintype "passive"))
      (node (ref "ZENER") (pin "A") (pinfunction "A_A") (pintype "passive"))
    )
    (net (code "55") (name "Net-(MIXA-A)") (class "Default")
      (node (ref "MIX") (pin "1") (pinfunction "A_1") (pintype "passive"))
      (node (ref "R17") (pin "1") (pinfunction "1_1") (pintype "passive"))
      (node (ref "R20") (pin "2") (pinfunction "2_2") (pintype "passive"))
    )
    (net (code "56") (name "Net-(MIXA-E)") (class "Default")
      (node (ref "MIX") (pin "3") (pinfunction "E_3") (pintype "passive"))
      (node (ref "R19") (pin "2") (pinfunction "2_2") (pintype "passive"))
      (node (ref "R4") (pin "1") (pinfunction "1_1") (pintype "passive"))
    )
    (net (code "57") (name "Net-(MIXB-E)") (class "Default")
      (node (ref "MIX") (pin "3B") (pinfunction "E_3B") (pintype "passive"))
      (node (ref "U$3") (pin "1") (pinfunction "1_1") (pintype "passive"))
      (node (ref "VOLUME") (pin "3B") (pinfunction "E_3B") (pintype "passive"))
    )
    (net (code "58") (name "Net-(MIXB-S)") (class "Default")
      (node (ref "JP3") (pin "4") (pinfunction "4_4") (pintype "passive"))
      (node (ref "MIX") (pin "2B") (pinfunction "S_2B") (pintype "passive"))
    )
    (net (code "59") (name "Net-(R13-Pad1)") (class "Default")
      (node (ref "R13") (pin "1") (pinfunction "1_1") (pintype "passive"))
      (node (ref "R16") (pin "A") (pinfunction "A_A") (pintype "passive"))
    )
    (net (code "60") (name "Net-(R16-PadS)") (class "Default")
      (node (ref "R16") (pin "S") (pinfunction "S_S") (pintype "passive"))
      (node (ref "ZENER") (pin "C") (pinfunction "C_C") (pintype "passive"))
    )
    (net (code "61") (name "Net-(RELAYA-P)") (class "Default")
      (node (ref "C1") (pin "1") (pinfunction "1_1") (pintype "passive"))
      (node (ref "R1") (pin "2") (pinfunction "2_2") (pintype "passive"))
      (node (ref "RELAY") (pin "3") (pinfunction "P_3") (pintype "passive"))
    )
    (net (code "62") (name "Net-(RELAYA-S)") (class "Default")
      (node (ref "IN") (pin "1") (pinfunction "1_1") (pintype "passive"))
      (node (ref "RELAY") (pin "4") (pinfunction "S_4") (pintype "passive"))
      (node (ref "RELAY") (pin "9") (pinfunction "O_9") (pintype "passive"))
    )
    (net (code "63") (name "Net-(RELAYB-S)") (class "Default")
      (node (ref "C24") (pin "2") (pinfunction "2_2") (pintype "passive"))
      (node (ref "R11") (pin "2") (pinfunction "2_2") (pintype "passive"))
      (node (ref "RELAY") (pin "7") (pinfunction "S_7") (pintype "passive"))
    )
    (net (code "64") (name "Net-(RELAYC-+)") (class "Default")
      (node (ref "RELAY") (pin "1") (pinfunction "+_1") (pintype "passive"))
      (node (ref "TINY85") (pin "3") (pinfunction "PB4_3") (pintype "bidirectional"))
    )
    (net (code "65") (name "Net-(RELAYC--)") (class "Default")
      (node (ref "RELAY") (pin "10") (pinfunction "-_10") (pintype "passive"))
      (node (ref "TINY85") (pin "5") (pinfunction "PB0_5") (pintype "bidirectional"))
    )
    (net (code "66") (name "Net-(TINY85-NRES{slash}PB5)") (class "Default")
      (node (ref "R7") (pin "1") (pinfunction "1_1") (pintype "passive"))
      (node (ref "TINY85") (pin "1") (pinfunction "NRES/PB5_1") (pintype "bidirectional"))
    )
    (net (code "67") (name "Net-(TINY85-PB2)") (class "Default")
      (node (ref "R26") (pin "1") (pinfunction "1_1") (pintype "passive"))
      (node (ref "TINY85") (pin "7") (pinfunction "PB2_7") (pintype "bidirectional"))
    )
    (net (code "68") (name "Net-(TINY85-PB3)") (class "Default")
      (node (ref "JP2") (pin "1") (pinfunction "1_1") (pintype "passive"))
      (node (ref "TINY85") (pin "2") (pinfunction "PB3_2") (pintype "bidirectional"))
    )
    (net (code "69") (name "Net-(VOLUMEB-S)") (class "Default")
      (node (ref "JP3") (pin "5") (pinfunction "5_5") (pintype "passive"))
      (node (ref "VOLUME") (pin "2B") (pinfunction "S_2B") (pintype "passive"))
    )
    (net (code "70") (name "unconnected-(IC1--IN-Pad2)") (class "Default")
      (node (ref "IC1") (pin "2") (pinfunction "-IN_2") (pintype "input"))
    )
    (net (code "71") (name "unconnected-(IC1-BYPASS-Pad7)") (class "Default")
      (node (ref "IC1") (pin "7") (pinfunction "BYPASS_7") (pintype "passive"))
    )
    (net (code "72") (name "unconnected-(IC1-GAIN-Pad1)") (class "Default")
      (node (ref "IC1") (pin "1") (pinfunction "GAIN_1") (pintype "passive"))
    )
    (net (code "73") (name "unconnected-(IC1-GAIN-Pad8)") (class "Default")
      (node (ref "IC1") (pin "8") (pinfunction "GAIN_8") (pintype "passive"))
    )
    (net (code "74") (name "unconnected-(IC3-P$27-Pad27)") (class "Default")
      (node (ref "IC3") (pin "27") (pinfunction "P$27_27") (pintype "bidirectional"))
    )
    (net (code "75") (name "unconnected-(J1-PadT_IRQ)") (class "Default")
      (node (ref "J1") (pin "T_IRQ") (pinfunction "T_IRQ_T_IRQ") (pintype "bidirectional"))
    )
    (net (code "76") (name "unconnected-(SDTFT-Pad1)") (class "Default")
      (node (ref "SDTFT") (pin "1") (pinfunction "1_1") (pintype "bidirectional"))
    )
    (net (code "77") (name "unconnected-(SDTFT-Pad2)") (class "Default")
      (node (ref "SDTFT") (pin "2") (pinfunction "2_2") (pintype "bidirectional"))
    )
    (net (code "78") (name "unconnected-(SDTFT-Pad3)") (class "Default")
      (node (ref "SDTFT") (pin "3") (pinfunction "3_3") (pintype "bidirectional"))
    )
    (net (code "79") (name "unconnected-(SDTFT-Pad4)") (class "Default")
      (node (ref "SDTFT") (pin "4") (pinfunction "4_4") (pintype "bidirectional"))
    )
    (net (code "80") (name "unconnected-(TINY85-PB1-Pad6)") (class "Default")
      (node (ref "TINY85") (pin "6") (pinfunction "PB1_6") (pintype "bidirectional"))
    )
    (net (code "81") (name "unconnected-(U$1-3.3V-PadP$23)") (class "Default")
      (node (ref "U$1") (pin "P$23") (pinfunction "3.3V_P$23") (pintype "bidirectional"))
    )
    (net (code "82") (name "unconnected-(U$1-3.3V1-PadP$20)") (class "Default")
      (node (ref "U$1") (pin "P$20") (pinfunction "3.3V1_P$20") (pintype "bidirectional"))
    )
    (net (code "83") (name "unconnected-(U$1-5V-PadP$18)") (class "Default")
      (node (ref "U$1") (pin "P$18") (pinfunction "5V_P$18") (pintype "bidirectional"))
    )
    (net (code "84") (name "unconnected-(U$1-GND-PadP$22)") (class "Default")
      (node (ref "U$1") (pin "P$22") (pinfunction "GND_P$22") (pintype "bidirectional"))
    )
    (net (code "85") (name "unconnected-(U$1-GND2-PadP$19)") (class "Default")
      (node (ref "U$1") (pin "P$19") (pinfunction "GND2_P$19") (pintype "bidirectional"))
    )
    (net (code "86") (name "unconnected-(U$1-PA0-PadP$36)") (class "Default")
      (node (ref "U$1") (pin "P$36") (pinfunction "PA0_P$36") (pintype "bidirectional"))
    )
    (net (code "87") (name "unconnected-(U$1-PA1-PadP$35)") (class "Default")
      (node (ref "U$1") (pin "P$35") (pinfunction "PA1_P$35") (pintype "bidirectional"))
    )
    (net (code "88") (name "unconnected-(U$1-PA2-PadP$34)") (class "Default")
      (node (ref "U$1") (pin "P$34") (pinfunction "PA2_P$34") (pintype "bidirectional"))
    )
    (net (code "89") (name "unconnected-(U$1-PA3-PadP$33)") (class "Default")
      (node (ref "U$1") (pin "P$33") (pinfunction "PA3_P$33") (pintype "bidirectional"))
    )
    (net (code "90") (name "unconnected-(U$1-PA4-PadP$32)") (class "Default")
      (node (ref "U$1") (pin "P$32") (pinfunction "PA4_P$32") (pintype "bidirectional"))
    )
    (net (code "91") (name "unconnected-(U$1-PA5-PadP$31)") (class "Default")
      (node (ref "U$1") (pin "P$31") (pinfunction "PA5_P$31") (pintype "bidirectional"))
    )
    (net (code "92") (name "unconnected-(U$1-PA6-PadP$30)") (class "Default")
      (node (ref "U$1") (pin "P$30") (pinfunction "PA6_P$30") (pintype "bidirectional"))
    )
    (net (code "93") (name "unconnected-(U$1-PA7-PadP$29)") (class "Default")
      (node (ref "U$1") (pin "P$29") (pinfunction "PA7_P$29") (pintype "bidirectional"))
    )
    (net (code "94") (name "unconnected-(U$1-PA8-PadP$5)") (class "Default")
      (node (ref "U$1") (pin "P$5") (pinfunction "PA8_P$5") (pintype "bidirectional"))
    )
    (net (code "95") (name "unconnected-(U$1-PA9-PadP$6)") (class "Default")
      (node (ref "U$1") (pin "P$6") (pinfunction "PA9_P$6") (pintype "bidirectional"))
    )
    (net (code "96") (name "unconnected-(U$1-PA10-PadP$7)") (class "Default")
      (node (ref "U$1") (pin "P$7") (pinfunction "PA10_P$7") (pintype "bidirectional"))
    )
    (net (code "97") (name "unconnected-(U$1-PA11-PadP$8)") (class "Default")
      (node (ref "U$1") (pin "P$8") (pinfunction "PA11_P$8") (pintype "bidirectional"))
    )
    (net (code "98") (name "unconnected-(U$1-PA12-PadP$9)") (class "Default")
      (node (ref "U$1") (pin "P$9") (pinfunction "PA12_P$9") (pintype "bidirectional"))
    )
    (net (code "99") (name "unconnected-(U$1-PA15-PadP$10)") (class "Default")
      (node (ref "U$1") (pin "P$10") (pinfunction "PA15_P$10") (pintype "bidirectional"))
    )
    (net (code "100") (name "unconnected-(U$1-PB0-PadP$28)") (class "Default")
      (node (ref "U$1") (pin "P$28") (pinfunction "PB0_P$28") (pintype "bidirectional"))
    )
    (net (code "101") (name "unconnected-(U$1-PB1-PadP$27)") (class "Default")
      (node (ref "U$1") (pin "P$27") (pinfunction "PB1_P$27") (pintype "bidirectional"))
    )
    (net (code "102") (name "unconnected-(U$1-PB3-PadP$11)") (class "Default")
      (node (ref "U$1") (pin "P$11") (pinfunction "PB3_P$11") (pintype "bidirectional"))
    )
    (net (code "103") (name "unconnected-(U$1-PB4-PadP$12)") (class "Default")
      (node (ref "U$1") (pin "P$12") (pinfunction "PB4_P$12") (pintype "bidirectional"))
    )
    (net (code "104") (name "unconnected-(U$1-PB5-PadP$13)") (class "Default")
      (node (ref "U$1") (pin "P$13") (pinfunction "PB5_P$13") (pintype "bidirectional"))
    )
    (net (code "105") (name "unconnected-(U$1-PB6-PadP$14)") (class "Default")
      (node (ref "U$1") (pin "P$14") (pinfunction "PB6_P$14") (pintype "bidirectional"))
    )
    (net (code "106") (name "unconnected-(U$1-PB7-PadP$15)") (class "Default")
      (node (ref "U$1") (pin "P$15") (pinfunction "PB7_P$15") (pintype "bidirectional"))
    )
    (net (code "107") (name "unconnected-(U$1-PB8-PadP$16)") (class "Default")
      (node (ref "U$1") (pin "P$16") (pinfunction "PB8_P$16") (pintype "bidirectional"))
    )
    (net (code "108") (name "unconnected-(U$1-PB9-PadP$17)") (class "Default")
      (node (ref "U$1") (pin "P$17") (pinfunction "PB9_P$17") (pintype "bidirectional"))
    )
    (net (code "109") (name "unconnected-(U$1-PB10-PadP$26)") (class "Default")
      (node (ref "U$1") (pin "P$26") (pinfunction "PB10_P$26") (pintype "bidirectional"))
    )
    (net (code "110") (name "unconnected-(U$1-PB11-PadP$25)") (class "Default")
      (node (ref "U$1") (pin "P$25") (pinfunction "PB11_P$25") (pintype "bidirectional"))
    )
    (net (code "111") (name "unconnected-(U$1-PB12-PadP$1)") (class "Default")
      (node (ref "U$1") (pin "P$1") (pinfunction "PB12_P$1") (pintype "bidirectional"))
    )
    (net (code "112") (name "unconnected-(U$1-PB13-PadP$2)") (class "Default")
      (node (ref "U$1") (pin "P$2") (pinfunction "PB13_P$2") (pintype "bidirectional"))
    )
    (net (code "113") (name "unconnected-(U$1-PB14-PadP$3)") (class "Default")
      (node (ref "U$1") (pin "P$3") (pinfunction "PB14_P$3") (pintype "bidirectional"))
    )
    (net (code "114") (name "unconnected-(U$1-PB15-PadP$4)") (class "Default")
      (node (ref "U$1") (pin "P$4") (pinfunction "PB15_P$4") (pintype "bidirectional"))
    )
    (net (code "115") (name "unconnected-(U$1-PC13-PadP$39)") (class "Default")
      (node (ref "U$1") (pin "P$39") (pinfunction "PC13_P$39") (pintype "bidirectional"))
    )
    (net (code "116") (name "unconnected-(U$1-PC14-PadP$38)") (class "Default")
      (node (ref "U$1") (pin "P$38") (pinfunction "PC14_P$38") (pintype "bidirectional"))
    )
    (net (code "117") (name "unconnected-(U$1-PC15-PadP$37)") (class "Default")
      (node (ref "U$1") (pin "P$37") (pinfunction "PC15_P$37") (pintype "bidirectional"))
    )
    (net (code "118") (name "unconnected-(U$1-RESET-PadP$24)") (class "Default")
      (node (ref "U$1") (pin "P$24") (pinfunction "RESET_P$24") (pintype "bidirectional"))
    )
    (net (code "119") (name "unconnected-(U$1-VBAT-PadP$40)") (class "Default")
      (node (ref "U$1") (pin "P$40") (pinfunction "VBAT_P$40") (pintype "bidirectional"))
    )
  )
)
